# HB-UNI-SEN-CAP-MOIST.net
KiCad netlist of a schematic drawn in EAGLE
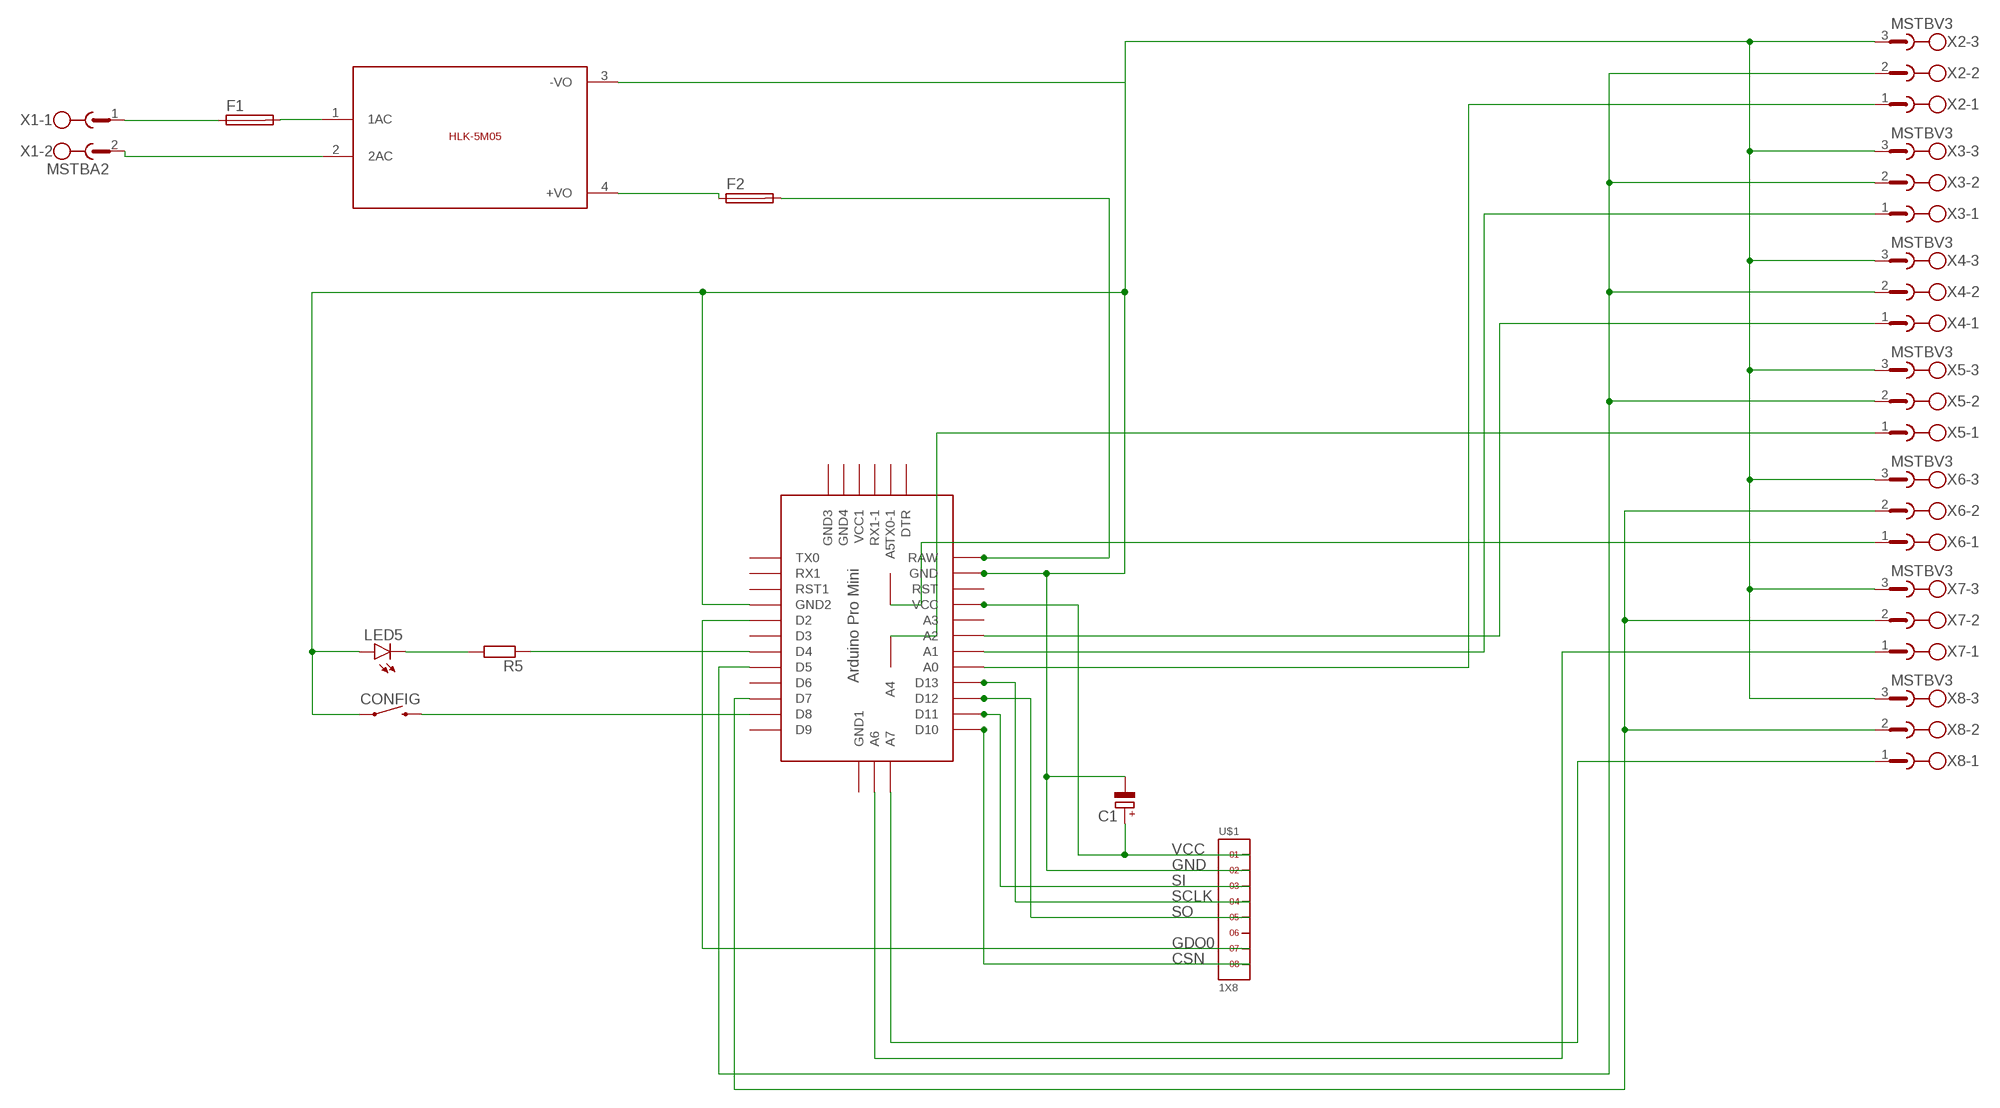
[diagram p0: schematic, sheet 1]

(export (version "E")
  (design (tool "Eeschema 10.0.6"))
  (components
    (comp (ref "C1")
      (value "CPOL-EUE2.5-5")
      (footprint "eagle-import:E2,5-5")
      (libsource (lib "eagle-import") (part "CPOL-EUE2.5-5"))
    )
    (comp (ref "CONFIG")
      (value "MOMENTARY-SWITCH-SPST-PTH-6.0MM-KIT")
      (footprint "eagle-import:TACTILE_SWITCH_PTH_6.0MM_KIT")
      (libsource (lib "eagle-import") (part "MOMENTARY-SWITCH-SPST-PTH-6.0MM-KIT"))
    )
    (comp (ref "F1")
      (value "SH22,5A")
      (footprint "eagle-import:SH22,5A")
      (fields (field (name "MPN") "0031.7701.11"))
      (libsource (lib "eagle-import") (part "SH22,5A"))
    )
    (comp (ref "F2")
      (value "SH22,5A")
      (footprint "eagle-import:SH22,5A")
      (fields (field (name "MPN") "0031.7701.11"))
      (libsource (lib "eagle-import") (part "SH22,5A"))
    )
    (comp (ref "LED5")
      (value "LED3MM")
      (footprint "eagle-import:LED3MM")
      (libsource (lib "eagle-import") (part "LED3MM"))
    )
    (comp (ref "R5")
      (value "R-EU_0309/10")
      (footprint "eagle-import:0309_10")
      (libsource (lib "eagle-import") (part "R-EU_0309/10"))
    )
    (comp (ref "U$1")
      (value "1X8")
      (footprint "eagle-import:1X8")
      (libsource (lib "eagle-import") (part "1X8"))
    )
    (comp (ref "U$2")
      (value "ABK-PRO-MINI")
      (footprint "eagle-import:ABK-PRO-MINI")
      (libsource (lib "eagle-import") (part "ABK-PRO-MINI"))
    )
    (comp (ref "U$3")
      (value "5VDC/5W")
      (footprint "eagle-import:HLK-5M05")
      (libsource (lib "eagle-import") (part "HLK-5M05"))
    )
    (comp (ref "X1")
      (value "MSTBA2")
      (footprint "eagle-import:MSTBA2")
      (fields (field (name "MF") "FARNELL") (field (name "MPN") "1757242"))
      (libsource (lib "eagle-import") (part "MSTBA2"))
    )
    (comp (ref "X2")
      (value "MSTBV3")
      (footprint "eagle-import:MSTBV3")
      (fields (field (name "MPN") "MSTBV 2,5/3-GF-5.08"))
      (libsource (lib "eagle-import") (part "MSTBV3"))
    )
    (comp (ref "X3")
      (value "MSTBV3")
      (footprint "eagle-import:MSTBV3")
      (fields (field (name "MPN") "MSTBV 2,5/3-GF-5.08"))
      (libsource (lib "eagle-import") (part "MSTBV3"))
    )
    (comp (ref "X4")
      (value "MSTBV3")
      (footprint "eagle-import:MSTBV3")
      (fields (field (name "MPN") "MSTBV 2,5/3-GF-5.08"))
      (libsource (lib "eagle-import") (part "MSTBV3"))
    )
    (comp (ref "X5")
      (value "MSTBV3")
      (footprint "eagle-import:MSTBV3")
      (fields (field (name "MPN") "MSTBV 2,5/3-GF-5.08"))
      (libsource (lib "eagle-import") (part "MSTBV3"))
    )
    (comp (ref "X6")
      (value "MSTBV3")
      (footprint "eagle-import:MSTBV3")
      (fields (field (name "MPN") "MSTBV 2,5/3-GF-5.08"))
      (libsource (lib "eagle-import") (part "MSTBV3"))
    )
    (comp (ref "X7")
      (value "MSTBV3")
      (footprint "eagle-import:MSTBV3")
      (fields (field (name "MPN") "MSTBV 2,5/3-GF-5.08"))
      (libsource (lib "eagle-import") (part "MSTBV3"))
    )
    (comp (ref "X8")
      (value "MSTBV3")
      (footprint "eagle-import:MSTBV3")
      (fields (field (name "MPN") "MSTBV 2,5/3-GF-5.08"))
      (libsource (lib "eagle-import") (part "MSTBV3"))
    )
  )
  (nets
    (net (code "1") (name "/CSN") (class "Default")
      (node (ref "U$1") (pin "8") (pinfunction "8_8") (pintype "bidirectional"))
      (node (ref "U$2") (pin "D10") (pinfunction "D10_D10") (pintype "bidirectional"))
    )
    (net (code "2") (name "/GDO0") (class "Default")
      (node (ref "U$1") (pin "7") (pinfunction "7_7") (pintype "bidirectional"))
      (node (ref "U$2") (pin "D2") (pinfunction "D2_D2") (pintype "bidirectional"))
    )
    (net (code "3") (name "/GND") (class "Default")
      (node (ref "C1") (pin "-") (pinfunction "-_-") (pintype "passive"))
      (node (ref "CONFIG") (pin "1") (pinfunction "1_1") (pintype "passive"))
      (node (ref "LED5") (pin "A") (pinfunction "A_A") (pintype "passive"))
      (node (ref "U$1") (pin "2") (pinfunction "2_2") (pintype "bidirectional"))
      (node (ref "U$2") (pin "GND") (pinfunction "GND_GND") (pintype "bidirectional"))
      (node (ref "U$2") (pin "GND1") (pinfunction "GND2_GND1") (pintype "bidirectional"))
      (node (ref "U$3") (pin "3") (pinfunction "-VO_3") (pintype "bidirectional"))
      (node (ref "X2") (pin "3") (pinfunction "1_3") (pintype "passive"))
      (node (ref "X3") (pin "3") (pinfunction "1_3") (pintype "passive"))
      (node (ref "X4") (pin "3") (pinfunction "1_3") (pintype "passive"))
      (node (ref "X5") (pin "3") (pinfunction "1_3") (pintype "passive"))
      (node (ref "X6") (pin "3") (pinfunction "1_3") (pintype "passive"))
      (node (ref "X7") (pin "3") (pinfunction "1_3") (pintype "passive"))
      (node (ref "X8") (pin "3") (pinfunction "1_3") (pintype "passive"))
    )
    (net (code "4") (name "/SCLK") (class "Default")
      (node (ref "U$1") (pin "4") (pinfunction "4_4") (pintype "bidirectional"))
      (node (ref "U$2") (pin "D13") (pinfunction "D13_D13") (pintype "bidirectional"))
    )
    (net (code "5") (name "/SI") (class "Default")
      (node (ref "U$1") (pin "3") (pinfunction "3_3") (pintype "bidirectional"))
      (node (ref "U$2") (pin "D11") (pinfunction "D11_D11") (pintype "bidirectional"))
    )
    (net (code "6") (name "/SO") (class "Default")
      (node (ref "U$1") (pin "5") (pinfunction "5_5") (pintype "bidirectional"))
      (node (ref "U$2") (pin "D12") (pinfunction "D12_D12") (pintype "bidirectional"))
    )
    (net (code "7") (name "/VCC") (class "Default")
      (node (ref "C1") (pin "+") (pinfunction "+_+") (pintype "passive"))
      (node (ref "U$1") (pin "1") (pinfunction "1_1") (pintype "bidirectional"))
      (node (ref "U$2") (pin "VCC") (pinfunction "VCC_VCC") (pintype "bidirectional"))
    )
    (net (code "8") (name "Net-(CONFIG-2)") (class "Default")
      (node (ref "CONFIG") (pin "3") (pinfunction "2_3") (pintype "passive"))
      (node (ref "U$2") (pin "D8") (pinfunction "D8_D8") (pintype "bidirectional"))
    )
    (net (code "9") (name "Net-(F1-Pad1)") (class "Default")
      (node (ref "F1") (pin "1") (pinfunction "1_1") (pintype "passive"))
      (node (ref "X1") (pin "1") (pinfunction "1_1") (pintype "passive"))
    )
    (net (code "10") (name "Net-(F2-Pad2)") (class "Default")
      (node (ref "F2") (pin "2") (pinfunction "2_2") (pintype "passive"))
      (node (ref "U$2") (pin "RAW") (pinfunction "RAW_RAW") (pintype "bidirectional"))
    )
    (net (code "11") (name "Net-(LED5-C)") (class "Default")
      (node (ref "LED5") (pin "K") (pinfunction "C_K") (pintype "passive"))
      (node (ref "R5") (pin "2") (pinfunction "2_2") (pintype "passive"))
    )
    (net (code "12") (name "Net-(R5-Pad1)") (class "Default")
      (node (ref "R5") (pin "1") (pinfunction "1_1") (pintype "passive"))
      (node (ref "U$2") (pin "D4") (pinfunction "D4_D4") (pintype "bidirectional"))
    )
    (net (code "13") (name "Net-(U$2-PadA0)") (class "Default")
      (node (ref "U$2") (pin "A0") (pinfunction "A0_A0") (pintype "bidirectional"))
      (node (ref "X2") (pin "1") (pinfunction "1_1") (pintype "passive"))
    )
    (net (code "14") (name "Net-(U$2-PadA1)") (class "Default")
      (node (ref "U$2") (pin "A1") (pinfunction "A1_A1") (pintype "bidirectional"))
      (node (ref "X3") (pin "1") (pinfunction "1_1") (pintype "passive"))
    )
    (net (code "15") (name "Net-(U$2-PadA2)") (class "Default")
      (node (ref "U$2") (pin "A2") (pinfunction "A2_A2") (pintype "bidirectional"))
      (node (ref "X4") (pin "1") (pinfunction "1_1") (pintype "passive"))
    )
    (net (code "16") (name "Net-(U$2-PadA4)") (class "Default")
      (node (ref "U$2") (pin "A4") (pinfunction "A4_A4") (pintype "bidirectional"))
      (node (ref "X5") (pin "1") (pinfunction "1_1") (pintype "passive"))
    )
    (net (code "17") (name "Net-(U$2-PadA5)") (class "Default")
      (node (ref "U$2") (pin "A5") (pinfunction "A5_A5") (pintype "bidirectional"))
      (node (ref "X6") (pin "1") (pinfunction "1_1") (pintype "passive"))
    )
    (net (code "18") (name "Net-(U$2-PadA6)") (class "Default")
      (node (ref "U$2") (pin "A6") (pinfunction "A6_A6") (pintype "bidirectional"))
      (node (ref "X7") (pin "1") (pinfunction "1_1") (pintype "passive"))
    )
    (net (code "19") (name "Net-(U$2-PadA7)") (class "Default")
      (node (ref "U$2") (pin "A7") (pinfunction "A7_A7") (pintype "bidirectional"))
      (node (ref "X8") (pin "1") (pinfunction "1_1") (pintype "passive"))
    )
    (net (code "20") (name "Net-(U$3-+VO)") (class "Default")
      (node (ref "F2") (pin "1") (pinfunction "1_1") (pintype "passive"))
      (node (ref "U$3") (pin "4") (pinfunction "+VO_4") (pintype "bidirectional"))
    )
    (net (code "21") (name "Net-(U$3-1AC)") (class "Default")
      (node (ref "F1") (pin "2") (pinfunction "2_2") (pintype "passive"))
      (node (ref "U$3") (pin "1") (pinfunction "1AC_1") (pintype "bidirectional"))
    )
    (net (code "22") (name "Net-(U$3-2AC)") (class "Default")
      (node (ref "U$3") (pin "2") (pinfunction "2AC_2") (pintype "bidirectional"))
      (node (ref "X1") (pin "2") (pinfunction "1_2") (pintype "passive"))
    )
    (net (code "23") (name "Net-(X2B-1)") (class "Default")
      (node (ref "U$2") (pin "D5") (pinfunction "D5_D5") (pintype "bidirectional"))
      (node (ref "X2") (pin "2") (pinfunction "1_2") (pintype "passive"))
      (node (ref "X3") (pin "2") (pinfunction "1_2") (pintype "passive"))
      (node (ref "X4") (pin "2") (pinfunction "1_2") (pintype "passive"))
      (node (ref "X5") (pin "2") (pinfunction "1_2") (pintype "passive"))
    )
    (net (code "24") (name "Net-(X6B-1)") (class "Default")
      (node (ref "U$2") (pin "D7") (pinfunction "D7_D7") (pintype "bidirectional"))
      (node (ref "X6") (pin "2") (pinfunction "1_2") (pintype "passive"))
      (node (ref "X7") (pin "2") (pinfunction "1_2") (pintype "passive"))
      (node (ref "X8") (pin "2") (pinfunction "1_2") (pintype "passive"))
    )
    (net (code "25") (name "unconnected-(U$1-Pad6)") (class "Default")
      (node (ref "U$1") (pin "6") (pinfunction "6_6") (pintype "bidirectional"))
    )
    (net (code "26") (name "unconnected-(U$2-GND1-PadGND4)") (class "Default")
      (node (ref "U$2") (pin "GND4") (pinfunction "GND1_GND4") (pintype "bidirectional"))
    )
    (net (code "27") (name "unconnected-(U$2-GND3-PadGND2)") (class "Default")
      (node (ref "U$2") (pin "GND2") (pinfunction "GND3_GND2") (pintype "bidirectional"))
    )
    (net (code "28") (name "unconnected-(U$2-GND4-PadGND3)") (class "Default")
      (node (ref "U$2") (pin "GND3") (pinfunction "GND4_GND3") (pintype "bidirectional"))
    )
    (net (code "29") (name "unconnected-(U$2-PadA3)") (class "Default")
      (node (ref "U$2") (pin "A3") (pinfunction "A3_A3") (pintype "bidirectional"))
    )
    (net (code "30") (name "unconnected-(U$2-PadD3)") (class "Default")
      (node (ref "U$2") (pin "D3") (pinfunction "D3_D3") (pintype "bidirectional"))
    )
    (net (code "31") (name "unconnected-(U$2-PadD6)") (class "Default")
      (node (ref "U$2") (pin "D6") (pinfunction "D6_D6") (pintype "bidirectional"))
    )
    (net (code "32") (name "unconnected-(U$2-PadD9)") (class "Default")
      (node (ref "U$2") (pin "D9") (pinfunction "D9_D9") (pintype "bidirectional"))
    )
    (net (code "33") (name "unconnected-(U$2-PadDTR)") (class "Default")
      (node (ref "U$2") (pin "DTR") (pinfunction "DTR_DTR") (pintype "bidirectional"))
    )
    (net (code "34") (name "unconnected-(U$2-PadRST)") (class "Default")
      (node (ref "U$2") (pin "RST") (pinfunction "RST_RST") (pintype "bidirectional"))
    )
    (net (code "35") (name "unconnected-(U$2-PadRST1)") (class "Default")
      (node (ref "U$2") (pin "RST1") (pinfunction "RST1_RST1") (pintype "bidirectional"))
    )
    (net (code "36") (name "unconnected-(U$2-PadRX1)") (class "Default")
      (node (ref "U$2") (pin "RX1") (pinfunction "RX1_RX1") (pintype "bidirectional"))
    )
    (net (code "37") (name "unconnected-(U$2-PadRX1-1)") (class "Default")
      (node (ref "U$2") (pin "RX1-1") (pinfunction "RX1-1_RX1-1") (pintype "bidirectional"))
    )
    (net (code "38") (name "unconnected-(U$2-PadTX0)") (class "Default")
      (node (ref "U$2") (pin "TX0") (pinfunction "TX0_TX0") (pintype "bidirectional"))
    )
    (net (code "39") (name "unconnected-(U$2-PadTX0-1)") (class "Default")
      (node (ref "U$2") (pin "TX0-1") (pinfunction "TX0-1_TX0-1") (pintype "bidirectional"))
    )
    (net (code "40") (name "unconnected-(U$2-PadVCC1)") (class "Default")
      (node (ref "U$2") (pin "VCC1") (pinfunction "VCC1_VCC1") (pintype "bidirectional"))
    )
  )
)
